# mkuBoard-045-2B.net
KiCad netlist of a schematic drawn in EAGLE
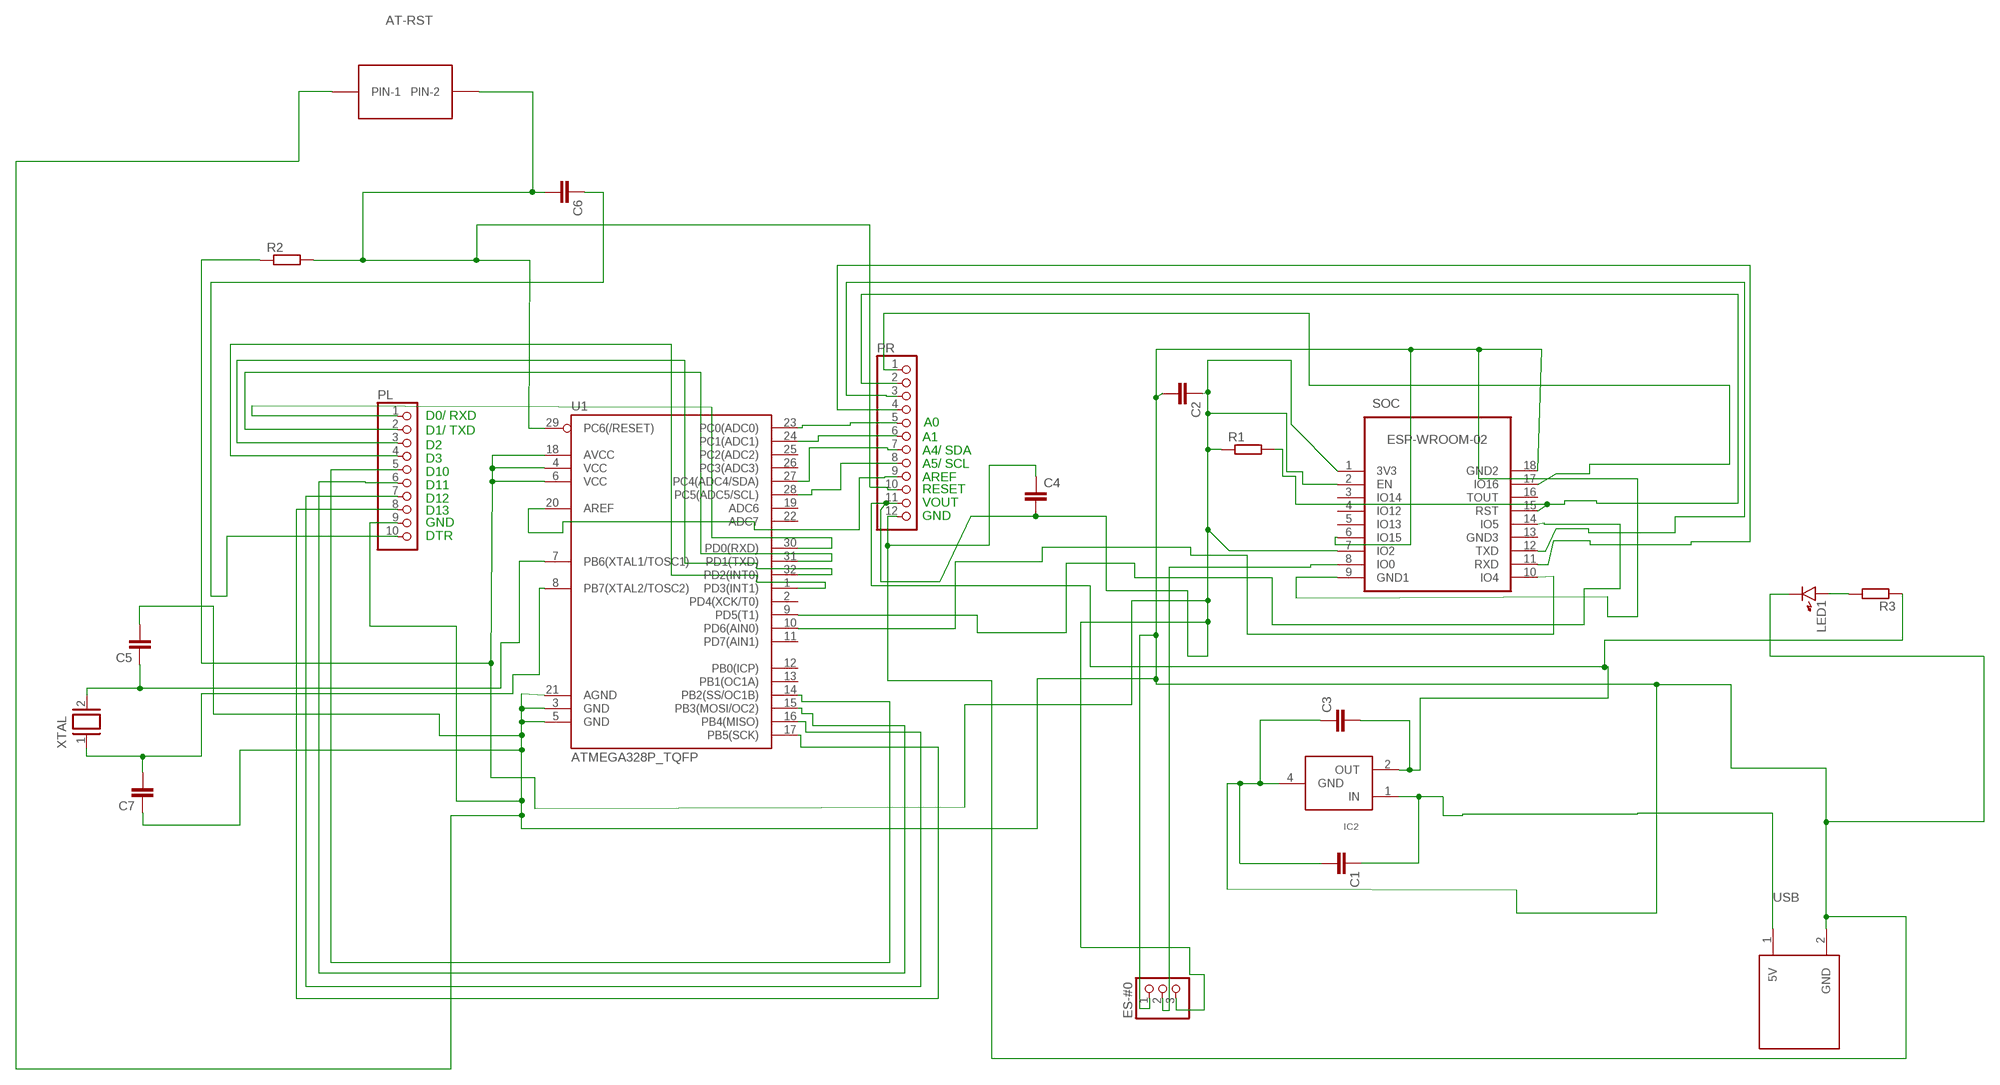
[diagram p0: schematic, sheet 1]

(export (version "E")
  (design (tool "Eeschema 10.0.6"))
  (components
    (comp (ref "AT-RST")
      (value "BTN2-EX")
      (footprint "eagle-import:B3F-10XX")
      (libsource (lib "eagle-import") (part "BTN2-EX"))
    )
    (comp (ref "C1")
      (value "C-EUC0603")
      (footprint "eagle-import:C0603")
      (libsource (lib "eagle-import") (part "C-EUC0603"))
    )
    (comp (ref "C2")
      (value "C-EUC0603")
      (footprint "eagle-import:C0603")
      (libsource (lib "eagle-import") (part "C-EUC0603"))
    )
    (comp (ref "C3")
      (value "C-EUC1206")
      (footprint "eagle-import:C1206")
      (libsource (lib "eagle-import") (part "C-EUC1206"))
    )
    (comp (ref "C4")
      (value "C-EUC1206")
      (footprint "eagle-import:C1206")
      (libsource (lib "eagle-import") (part "C-EUC1206"))
    )
    (comp (ref "C5")
      (value "C-EUC0603")
      (footprint "eagle-import:C0603")
      (libsource (lib "eagle-import") (part "C-EUC0603"))
    )
    (comp (ref "C6")
      (value "C-EUC0603")
      (footprint "eagle-import:C0603")
      (libsource (lib "eagle-import") (part "C-EUC0603"))
    )
    (comp (ref "C7")
      (value "C-EUC0603")
      (footprint "eagle-import:C0603")
      (libsource (lib "eagle-import") (part "C-EUC0603"))
    )
    (comp (ref "ES-#0")
      (value "PINHD-1X3")
      (footprint "eagle-import:1X03")
      (libsource (lib "eagle-import") (part "PINHD-1X3"))
    )
    (comp (ref "IC2")
      (value "NJM2845DL1")
      (footprint "eagle-import:NJM2845DL1-PKG")
      (libsource (lib "eagle-import") (part "NJM2845DL1"))
    )
    (comp (ref "LED1")
      (value "LED1608")
      (footprint "eagle-import:LED1608")
      (libsource (lib "eagle-import") (part "LED1608"))
    )
    (comp (ref "PL")
      (value "PINHD-1X10")
      (footprint "eagle-import:1X10")
      (libsource (lib "eagle-import") (part "PINHD-1X10"))
    )
    (comp (ref "PR")
      (value "PINHD-1X12")
      (footprint "eagle-import:1X12")
      (libsource (lib "eagle-import") (part "PINHD-1X12"))
    )
    (comp (ref "R1")
      (value "R-EU_R0603")
      (footprint "eagle-import:R0603")
      (libsource (lib "eagle-import") (part "R-EU_R0603"))
    )
    (comp (ref "R2")
      (value "R-EU_R0603")
      (footprint "eagle-import:R0603")
      (libsource (lib "eagle-import") (part "R-EU_R0603"))
    )
    (comp (ref "R3")
      (value "R-EU_R0603")
      (footprint "eagle-import:R0603")
      (libsource (lib "eagle-import") (part "R-EU_R0603"))
    )
    (comp (ref "SOC")
      (value "ESP-WROOM-02")
      (footprint "eagle-import:FRONT-FACE-CP2")
      (libsource (lib "eagle-import") (part "ESP-WROOM-02-CP2FRONT"))
    )
    (comp (ref "U1")
      (value "ATMEGA328P_TQFP")
      (footprint "eagle-import:TQFP32-08")
      (libsource (lib "eagle-import") (part "ATMEGA328P_TQFP"))
    )
    (comp (ref "USB")
      (value "USB-CUST-1")
      (footprint "eagle-import:USB-CUST-1-PKG")
      (libsource (lib "eagle-import") (part "USB-CUST-1"))
    )
    (comp (ref "XTAL")
      (value "XTAL/S")
      (footprint "eagle-import:QS")
      (libsource (lib "eagle-import") (part "XTAL/S"))
    )
  )
  (nets
    (net (code "1") (name "Net-(AT-RST-PIN-1)") (class "Default")
      (node (ref "AT-RST") (pin "1") (pinfunction "PIN-1_1") (pintype "bidirectional"))
      (node (ref "C1") (pin "2") (pinfunction "2_2") (pintype "passive"))
      (node (ref "C2") (pin "2") (pinfunction "2_2") (pintype "passive"))
      (node (ref "C3") (pin "1") (pinfunction "1_1") (pintype "passive"))
      (node (ref "C4") (pin "1") (pinfunction "1_1") (pintype "passive"))
      (node (ref "C5") (pin "2") (pinfunction "2_2") (pintype "passive"))
      (node (ref "C7") (pin "1") (pinfunction "1_1") (pintype "passive"))
      (node (ref "ES-#0") (pin "1") (pinfunction "1_1") (pintype "passive"))
      (node (ref "IC2") (pin "4") (pinfunction "GND_4") (pintype "bidirectional"))
      (node (ref "LED1") (pin "K") (pinfunction "K_K") (pintype "passive"))
      (node (ref "PL") (pin "9") (pinfunction "9_9") (pintype "passive"))
      (node (ref "PR") (pin "12") (pinfunction "12_12") (pintype "passive"))
      (node (ref "SOC") (pin "18") (pinfunction "GND2_18") (pintype "bidirectional"))
      (node (ref "SOC") (pin "6") (pinfunction "IO15_6") (pintype "bidirectional"))
      (node (ref "SOC") (pin "9") (pinfunction "GND1_9") (pintype "bidirectional"))
      (node (ref "U1") (pin "21") (pinfunction "AGND_21") (pintype "bidirectional"))
      (node (ref "U1") (pin "3") (pinfunction "GND_3") (pintype "bidirectional"))
      (node (ref "U1") (pin "5") (pinfunction "GND_5") (pintype "bidirectional"))
      (node (ref "USB") (pin "2") (pinfunction "GND_2") (pintype "bidirectional"))
    )
    (net (code "2") (name "Net-(AT-RST-PIN-2)") (class "Default")
      (node (ref "AT-RST") (pin "2") (pinfunction "PIN-2_2") (pintype "bidirectional"))
      (node (ref "C6") (pin "2") (pinfunction "2_2") (pintype "passive"))
      (node (ref "PR") (pin "10") (pinfunction "10_10") (pintype "passive"))
      (node (ref "R2") (pin "2") (pinfunction "2_2") (pintype "passive"))
      (node (ref "U1") (pin "29") (pinfunction "PC6(/RESET)_29") (pintype "bidirectional"))
    )
    (net (code "3") (name "Net-(C6-Pad1)") (class "Default")
      (node (ref "C6") (pin "1") (pinfunction "1_1") (pintype "passive"))
      (node (ref "PL") (pin "10") (pinfunction "10_10") (pintype "passive"))
    )
    (net (code "4") (name "Net-(IC2-IN)") (class "Default")
      (node (ref "C1") (pin "1") (pinfunction "1_1") (pintype "passive"))
      (node (ref "IC2") (pin "1") (pinfunction "IN_1") (pintype "bidirectional"))
      (node (ref "USB") (pin "1") (pinfunction "5V_1") (pintype "bidirectional"))
    )
    (net (code "5") (name "Net-(IC2-OUT)") (class "Default")
      (node (ref "C2") (pin "1") (pinfunction "1_1") (pintype "passive"))
      (node (ref "C3") (pin "2") (pinfunction "2_2") (pintype "passive"))
      (node (ref "C4") (pin "2") (pinfunction "2_2") (pintype "passive"))
      (node (ref "ES-#0") (pin "3") (pinfunction "3_3") (pintype "passive"))
      (node (ref "IC2") (pin "2") (pinfunction "OUT_2") (pintype "bidirectional"))
      (node (ref "PR") (pin "11") (pinfunction "11_11") (pintype "passive"))
      (node (ref "R1") (pin "1") (pinfunction "1_1") (pintype "passive"))
      (node (ref "R2") (pin "1") (pinfunction "1_1") (pintype "passive"))
      (node (ref "R3") (pin "1") (pinfunction "1_1") (pintype "passive"))
      (node (ref "SOC") (pin "1") (pinfunction "3V3_1") (pintype "bidirectional"))
      (node (ref "SOC") (pin "2") (pinfunction "EN_2") (pintype "bidirectional"))
      (node (ref "SOC") (pin "7") (pinfunction "IO2_7") (pintype "bidirectional"))
      (node (ref "U1") (pin "18") (pinfunction "AVCC_18") (pintype "bidirectional"))
      (node (ref "U1") (pin "4") (pinfunction "VCC_4") (pintype "bidirectional"))
      (node (ref "U1") (pin "6") (pinfunction "VCC_6") (pintype "bidirectional"))
    )
    (net (code "6") (name "Net-(LED1-PadA)") (class "Default")
      (node (ref "LED1") (pin "A") (pinfunction "A_A") (pintype "passive"))
      (node (ref "R3") (pin "2") (pinfunction "2_2") (pintype "passive"))
    )
    (net (code "7") (name "Net-(SOC-IO0)") (class "Default")
      (node (ref "ES-#0") (pin "2") (pinfunction "2_2") (pintype "passive"))
      (node (ref "SOC") (pin "8") (pinfunction "IO0_8") (pintype "bidirectional"))
    )
    (net (code "8") (name "Net-(SOC-IO4)") (class "Default")
      (node (ref "SOC") (pin "10") (pinfunction "IO4_10") (pintype "bidirectional"))
      (node (ref "U1") (pin "10") (pinfunction "PD6(AIN0)_10") (pintype "bidirectional"))
    )
    (net (code "9") (name "Net-(SOC-IO5)") (class "Default")
      (node (ref "SOC") (pin "14") (pinfunction "IO5_14") (pintype "bidirectional"))
      (node (ref "U1") (pin "9") (pinfunction "PD5(T1)_9") (pintype "bidirectional"))
    )
    (net (code "10") (name "Net-(SOC-IO16)") (class "Default")
      (node (ref "PR") (pin "1") (pinfunction "1_1") (pintype "passive"))
      (node (ref "SOC") (pin "17") (pinfunction "IO16_17") (pintype "bidirectional"))
    )
    (net (code "11") (name "Net-(SOC-RST)") (class "Default")
      (node (ref "PR") (pin "2") (pinfunction "2_2") (pintype "passive"))
      (node (ref "R1") (pin "2") (pinfunction "2_2") (pintype "passive"))
      (node (ref "SOC") (pin "15") (pinfunction "RST_15") (pintype "bidirectional"))
    )
    (net (code "12") (name "Net-(SOC-RXD)") (class "Default")
      (node (ref "PR") (pin "4") (pinfunction "4_4") (pintype "passive"))
      (node (ref "SOC") (pin "11") (pinfunction "RXD_11") (pintype "bidirectional"))
    )
    (net (code "13") (name "Net-(SOC-TXD)") (class "Default")
      (node (ref "PR") (pin "3") (pinfunction "3_3") (pintype "passive"))
      (node (ref "SOC") (pin "12") (pinfunction "TXD_12") (pintype "bidirectional"))
    )
    (net (code "14") (name "Net-(U1-AREF)") (class "Default")
      (node (ref "PR") (pin "9") (pinfunction "9_9") (pintype "passive"))
      (node (ref "U1") (pin "20") (pinfunction "AREF_20") (pintype "bidirectional"))
    )
    (net (code "15") (name "Net-(U1-PB2(SS{slash}OC1B))") (class "Default")
      (node (ref "PL") (pin "5") (pinfunction "5_5") (pintype "passive"))
      (node (ref "U1") (pin "14") (pinfunction "PB2(SS/OC1B)_14") (pintype "bidirectional"))
    )
    (net (code "16") (name "Net-(U1-PB3(MOSI{slash}OC2))") (class "Default")
      (node (ref "PL") (pin "6") (pinfunction "6_6") (pintype "passive"))
      (node (ref "U1") (pin "15") (pinfunction "PB3(MOSI/OC2)_15") (pintype "bidirectional"))
    )
    (net (code "17") (name "Net-(U1-PB4(MISO))") (class "Default")
      (node (ref "PL") (pin "7") (pinfunction "7_7") (pintype "passive"))
      (node (ref "U1") (pin "16") (pinfunction "PB4(MISO)_16") (pintype "bidirectional"))
    )
    (net (code "18") (name "Net-(U1-PB5(SCK))") (class "Default")
      (node (ref "PL") (pin "8") (pinfunction "8_8") (pintype "passive"))
      (node (ref "U1") (pin "17") (pinfunction "PB5(SCK)_17") (pintype "bidirectional"))
    )
    (net (code "19") (name "Net-(U1-PB6(XTAL1{slash}TOSC1))") (class "Default")
      (node (ref "C5") (pin "1") (pinfunction "1_1") (pintype "passive"))
      (node (ref "U1") (pin "7") (pinfunction "PB6(XTAL1/TOSC1)_7") (pintype "bidirectional"))
      (node (ref "XTAL") (pin "2") (pinfunction "2_2") (pintype "passive"))
    )
    (net (code "20") (name "Net-(U1-PB7(XTAL2{slash}TOSC2))") (class "Default")
      (node (ref "C7") (pin "2") (pinfunction "2_2") (pintype "passive"))
      (node (ref "U1") (pin "8") (pinfunction "PB7(XTAL2/TOSC2)_8") (pintype "bidirectional"))
      (node (ref "XTAL") (pin "1") (pinfunction "1_1") (pintype "passive"))
    )
    (net (code "21") (name "Net-(U1-PC0(ADC0))") (class "Default")
      (node (ref "PR") (pin "5") (pinfunction "5_5") (pintype "passive"))
      (node (ref "U1") (pin "23") (pinfunction "PC0(ADC0)_23") (pintype "bidirectional"))
    )
    (net (code "22") (name "Net-(U1-PC1(ADC1))") (class "Default")
      (node (ref "PR") (pin "6") (pinfunction "6_6") (pintype "passive"))
      (node (ref "U1") (pin "24") (pinfunction "PC1(ADC1)_24") (pintype "bidirectional"))
    )
    (net (code "23") (name "Net-(U1-PC4(ADC4{slash}SDA))") (class "Default")
      (node (ref "PR") (pin "7") (pinfunction "7_7") (pintype "passive"))
      (node (ref "U1") (pin "27") (pinfunction "PC4(ADC4/SDA)_27") (pintype "bidirectional"))
    )
    (net (code "24") (name "Net-(U1-PC5(ADC5{slash}SCL))") (class "Default")
      (node (ref "PR") (pin "8") (pinfunction "8_8") (pintype "passive"))
      (node (ref "U1") (pin "28") (pinfunction "PC5(ADC5/SCL)_28") (pintype "bidirectional"))
    )
    (net (code "25") (name "Net-(U1-PD0(RXD))") (class "Default")
      (node (ref "PL") (pin "1") (pinfunction "1_1") (pintype "passive"))
      (node (ref "U1") (pin "30") (pinfunction "PD0(RXD)_30") (pintype "bidirectional"))
    )
    (net (code "26") (name "Net-(U1-PD1(TXD))") (class "Default")
      (node (ref "PL") (pin "2") (pinfunction "2_2") (pintype "passive"))
      (node (ref "U1") (pin "31") (pinfunction "PD1(TXD)_31") (pintype "bidirectional"))
    )
    (net (code "27") (name "Net-(U1-PD2(INT0))") (class "Default")
      (node (ref "PL") (pin "3") (pinfunction "3_3") (pintype "passive"))
      (node (ref "U1") (pin "32") (pinfunction "PD2(INT0)_32") (pintype "bidirectional"))
    )
    (net (code "28") (name "Net-(U1-PD3(INT1))") (class "Default")
      (node (ref "PL") (pin "4") (pinfunction "4_4") (pintype "passive"))
      (node (ref "U1") (pin "1") (pinfunction "PD3(INT1)_1") (pintype "bidirectional"))
    )
    (net (code "29") (name "unconnected-(SOC-GND3-Pad13)") (class "Default")
      (node (ref "SOC") (pin "13") (pinfunction "GND3_13") (pintype "bidirectional"))
    )
    (net (code "30") (name "unconnected-(SOC-IO12-Pad4)") (class "Default")
      (node (ref "SOC") (pin "4") (pinfunction "IO12_4") (pintype "bidirectional"))
    )
    (net (code "31") (name "unconnected-(SOC-IO13-Pad5)") (class "Default")
      (node (ref "SOC") (pin "5") (pinfunction "IO13_5") (pintype "open_collector"))
    )
    (net (code "32") (name "unconnected-(SOC-IO14-Pad3)") (class "Default")
      (node (ref "SOC") (pin "3") (pinfunction "IO14_3") (pintype "bidirectional"))
    )
    (net (code "33") (name "unconnected-(SOC-TOUT-Pad16)") (class "Default")
      (node (ref "SOC") (pin "16") (pinfunction "TOUT_16") (pintype "bidirectional"))
    )
    (net (code "34") (name "unconnected-(U1-ADC6-Pad19)") (class "Default")
      (node (ref "U1") (pin "19") (pinfunction "ADC6_19") (pintype "bidirectional"))
    )
    (net (code "35") (name "unconnected-(U1-ADC7-Pad22)") (class "Default")
      (node (ref "U1") (pin "22") (pinfunction "ADC7_22") (pintype "bidirectional"))
    )
    (net (code "36") (name "unconnected-(U1-PB0(ICP)-Pad12)") (class "Default")
      (node (ref "U1") (pin "12") (pinfunction "PB0(ICP)_12") (pintype "bidirectional"))
    )
    (net (code "37") (name "unconnected-(U1-PB1(OC1A)-Pad13)") (class "Default")
      (node (ref "U1") (pin "13") (pinfunction "PB1(OC1A)_13") (pintype "bidirectional"))
    )
    (net (code "38") (name "unconnected-(U1-PC2(ADC2)-Pad25)") (class "Default")
      (node (ref "U1") (pin "25") (pinfunction "PC2(ADC2)_25") (pintype "bidirectional"))
    )
    (net (code "39") (name "unconnected-(U1-PC3(ADC3)-Pad26)") (class "Default")
      (node (ref "U1") (pin "26") (pinfunction "PC3(ADC3)_26") (pintype "bidirectional"))
    )
    (net (code "40") (name "unconnected-(U1-PD4(XCK{slash}T0)-Pad2)") (class "Default")
      (node (ref "U1") (pin "2") (pinfunction "PD4(XCK/T0)_2") (pintype "bidirectional"))
    )
    (net (code "41") (name "unconnected-(U1-PD7(AIN1)-Pad11)") (class "Default")
      (node (ref "U1") (pin "11") (pinfunction "PD7(AIN1)_11") (pintype "bidirectional"))
    )
  )
)
